# board.net
KiCad netlist of a schematic drawn in EAGLE
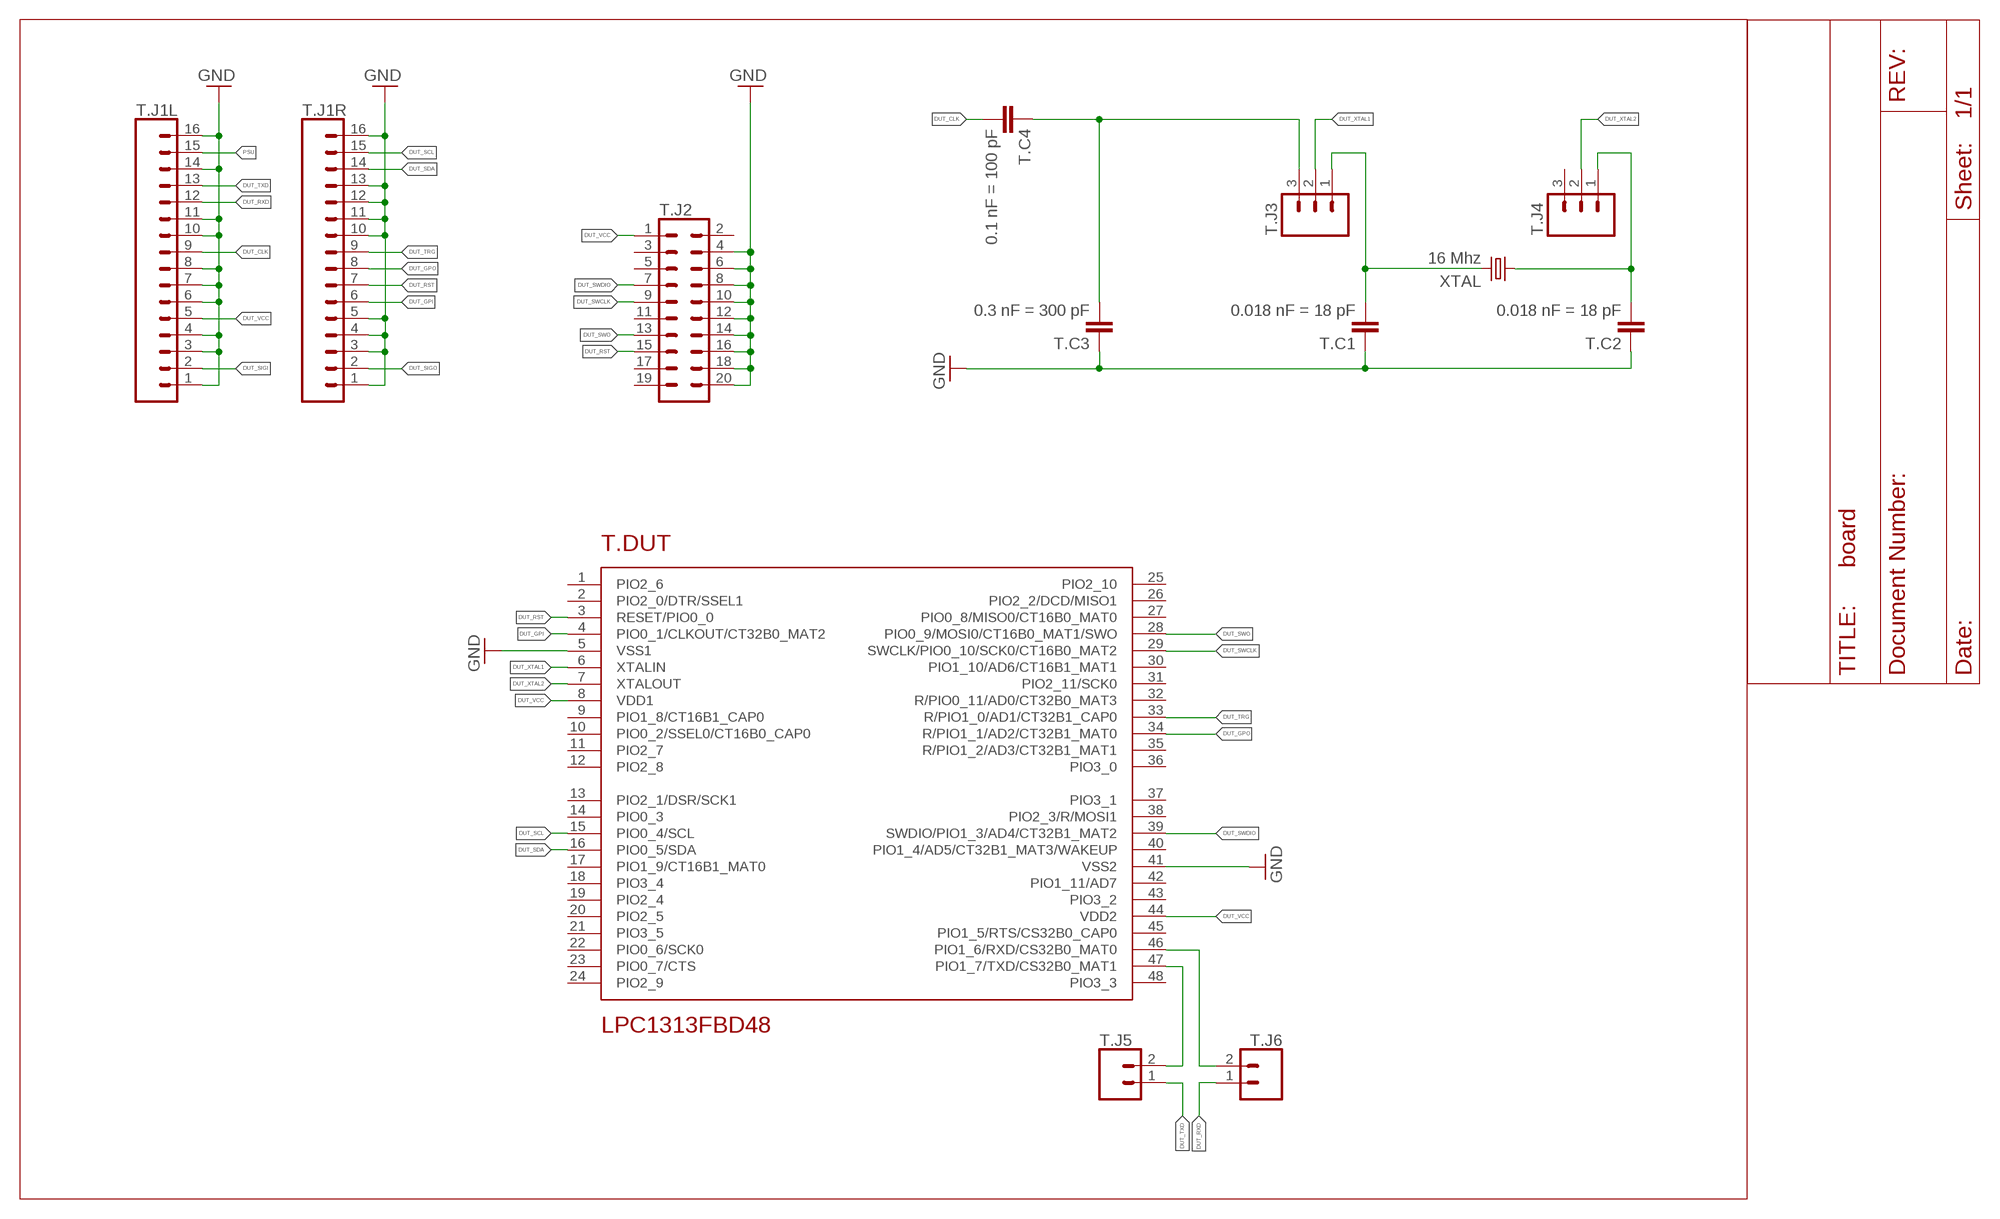
[diagram p0: schematic, sheet 1]

(export (version "E")
  (design (tool "Eeschema 10.0.6"))
  (components
    (comp (ref "T.C1")
      (value "0.018 nF = 18 pF")
      (footprint "eagle-import:0603-CAP")
      (libsource (lib "eagle-import") (part "CAP0603-CAP"))
    )
    (comp (ref "T.C2")
      (value "0.018 nF = 18 pF")
      (footprint "eagle-import:0603-CAP")
      (libsource (lib "eagle-import") (part "CAP0603-CAP"))
    )
    (comp (ref "T.C3")
      (value "0.3 nF = 300 pF")
      (footprint "eagle-import:0603-CAP")
      (libsource (lib "eagle-import") (part "CAP0603-CAP"))
    )
    (comp (ref "T.C4")
      (value "0.1 nF = 100 pF")
      (footprint "eagle-import:0603-CAP")
      (libsource (lib "eagle-import") (part "CAP0603-CAP"))
    )
    (comp (ref "T.DUT")
      (value "LPC1313FBD48")
      (footprint "eagle-import:LQFP48")
      (libsource (lib "eagle-import") (part "LPC1313FBD48"))
    )
    (comp (ref "T.J1L")
      (value "CONN_16")
      (footprint "eagle-import:1X16")
      (libsource (lib "eagle-import") (part "CONN_16"))
    )
    (comp (ref "T.J1R")
      (value "CONN_16")
      (footprint "eagle-import:1X16")
      (libsource (lib "eagle-import") (part "CONN_16"))
    )
    (comp (ref "T.J2")
      (value "CONN_10X2")
      (footprint "eagle-import:2X10")
      (libsource (lib "eagle-import") (part "CONN_10X2"))
    )
    (comp (ref "T.J3")
      (value "M03PTH")
      (footprint "eagle-import:1X03")
      (libsource (lib "eagle-import") (part "M03PTH"))
    )
    (comp (ref "T.J4")
      (value "M03PTH")
      (footprint "eagle-import:1X03")
      (libsource (lib "eagle-import") (part "M03PTH"))
    )
    (comp (ref "T.J5")
      (value "CONN_02")
      (footprint "eagle-import:1X02")
      (libsource (lib "eagle-import") (part "CONN_02"))
    )
    (comp (ref "T.J6")
      (value "CONN_02")
      (footprint "eagle-import:1X02")
      (libsource (lib "eagle-import") (part "CONN_02"))
    )
    (comp (ref "XTAL")
      (value "16 Mhz")
      (footprint "eagle-import:HC49US")
      (libsource (lib "eagle-import") (part "CRYSTALHC49US"))
    )
  )
  (nets
    (net (code "1") (name "DUT_CLK") (class "Default")
      (node (ref "T.C4") (pin "2") (pinfunction "2_2") (pintype "passive"))
      (node (ref "T.J1L") (pin "9") (pinfunction "9_9") (pintype "passive"))
    )
    (net (code "2") (name "DUT_GPI") (class "Default")
      (node (ref "T.DUT") (pin "4") (pinfunction "PIO0_1/CLKOUT/CT32B0_MAT2_4") (pintype "bidirectional"))
      (node (ref "T.J1R") (pin "6") (pinfunction "6_6") (pintype "passive"))
    )
    (net (code "3") (name "DUT_GPO") (class "Default")
      (node (ref "T.DUT") (pin "34") (pinfunction "R/PIO1_1/AD2/CT32B1_MAT0_34") (pintype "bidirectional"))
      (node (ref "T.J1R") (pin "8") (pinfunction "8_8") (pintype "passive"))
    )
    (net (code "4") (name "DUT_RST") (class "Default")
      (node (ref "T.DUT") (pin "3") (pinfunction "RESET/PIO0_0_3") (pintype "bidirectional"))
      (node (ref "T.J1R") (pin "7") (pinfunction "7_7") (pintype "passive"))
      (node (ref "T.J2") (pin "15") (pinfunction "15_15") (pintype "passive"))
    )
    (net (code "5") (name "DUT_RXD") (class "Default")
      (node (ref "T.J1L") (pin "12") (pinfunction "12_12") (pintype "passive"))
      (node (ref "T.J6") (pin "1") (pinfunction "1_1") (pintype "passive"))
    )
    (net (code "6") (name "DUT_SCL") (class "Default")
      (node (ref "T.DUT") (pin "15") (pinfunction "PIO0_4/SCL_15") (pintype "bidirectional"))
      (node (ref "T.J1R") (pin "15") (pinfunction "15_15") (pintype "passive"))
    )
    (net (code "7") (name "DUT_SDA") (class "Default")
      (node (ref "T.DUT") (pin "16") (pinfunction "PIO0_5/SDA_16") (pintype "bidirectional"))
      (node (ref "T.J1R") (pin "14") (pinfunction "14_14") (pintype "passive"))
    )
    (net (code "8") (name "DUT_SIGI") (class "Default")
      (node (ref "T.J1L") (pin "2") (pinfunction "2_2") (pintype "passive"))
    )
    (net (code "9") (name "DUT_SIGO") (class "Default")
      (node (ref "T.J1R") (pin "2") (pinfunction "2_2") (pintype "passive"))
    )
    (net (code "10") (name "DUT_SWCLK") (class "Default")
      (node (ref "T.DUT") (pin "29") (pinfunction "SWCLK/PIO0_10/SCK0/CT16B0_MAT2_29") (pintype "bidirectional"))
      (node (ref "T.J2") (pin "9") (pinfunction "9_9") (pintype "passive"))
    )
    (net (code "11") (name "DUT_SWDIO") (class "Default")
      (node (ref "T.DUT") (pin "39") (pinfunction "SWDIO/PIO1_3/AD4/CT32B1_MAT2_39") (pintype "bidirectional"))
      (node (ref "T.J2") (pin "7") (pinfunction "7_7") (pintype "passive"))
    )
    (net (code "12") (name "DUT_SWO") (class "Default")
      (node (ref "T.DUT") (pin "28") (pinfunction "PIO0_9/MOSI0/CT16B0_MAT1/SWO_28") (pintype "bidirectional"))
      (node (ref "T.J2") (pin "13") (pinfunction "13_13") (pintype "passive"))
    )
    (net (code "13") (name "DUT_TRG") (class "Default")
      (node (ref "T.DUT") (pin "33") (pinfunction "R/PIO1_0/AD1/CT32B1_CAP0_33") (pintype "bidirectional"))
      (node (ref "T.J1R") (pin "9") (pinfunction "9_9") (pintype "passive"))
    )
    (net (code "14") (name "DUT_TXD") (class "Default")
      (node (ref "T.J1L") (pin "13") (pinfunction "13_13") (pintype "passive"))
      (node (ref "T.J5") (pin "1") (pinfunction "1_1") (pintype "passive"))
    )
    (net (code "15") (name "DUT_VCC") (class "Default")
      (node (ref "T.DUT") (pin "44") (pinfunction "VDD2_44") (pintype "bidirectional"))
      (node (ref "T.DUT") (pin "8") (pinfunction "VDD1_8") (pintype "bidirectional"))
      (node (ref "T.J1L") (pin "5") (pinfunction "5_5") (pintype "passive"))
      (node (ref "T.J2") (pin "1") (pinfunction "1_1") (pintype "passive"))
    )
    (net (code "16") (name "DUT_XTAL1") (class "Default")
      (node (ref "T.DUT") (pin "6") (pinfunction "XTALIN_6") (pintype "bidirectional"))
      (node (ref "T.J3") (pin "2") (pinfunction "2_2") (pintype "passive"))
    )
    (net (code "17") (name "DUT_XTAL2") (class "Default")
      (node (ref "T.DUT") (pin "7") (pinfunction "XTALOUT_7") (pintype "bidirectional"))
      (node (ref "T.J4") (pin "2") (pinfunction "2_2") (pintype "passive"))
    )
    (net (code "18") (name "GND") (class "Default")
      (node (ref "T.C1") (pin "1") (pinfunction "1_1") (pintype "passive"))
      (node (ref "T.C2") (pin "1") (pinfunction "1_1") (pintype "passive"))
      (node (ref "T.C3") (pin "1") (pinfunction "1_1") (pintype "passive"))
      (node (ref "T.DUT") (pin "41") (pinfunction "VSS2_41") (pintype "bidirectional"))
      (node (ref "T.DUT") (pin "5") (pinfunction "VSS1_5") (pintype "bidirectional"))
      (node (ref "T.J1L") (pin "1") (pinfunction "1_1") (pintype "passive"))
      (node (ref "T.J1L") (pin "10") (pinfunction "10_10") (pintype "passive"))
      (node (ref "T.J1L") (pin "11") (pinfunction "11_11") (pintype "passive"))
      (node (ref "T.J1L") (pin "14") (pinfunction "14_14") (pintype "passive"))
      (node (ref "T.J1L") (pin "16") (pinfunction "16_16") (pintype "passive"))
      (node (ref "T.J1L") (pin "3") (pinfunction "3_3") (pintype "passive"))
      (node (ref "T.J1L") (pin "4") (pinfunction "4_4") (pintype "passive"))
      (node (ref "T.J1L") (pin "6") (pinfunction "6_6") (pintype "passive"))
      (node (ref "T.J1L") (pin "7") (pinfunction "7_7") (pintype "passive"))
      (node (ref "T.J1L") (pin "8") (pinfunction "8_8") (pintype "passive"))
      (node (ref "T.J1R") (pin "1") (pinfunction "1_1") (pintype "passive"))
      (node (ref "T.J1R") (pin "10") (pinfunction "10_10") (pintype "passive"))
      (node (ref "T.J1R") (pin "11") (pinfunction "11_11") (pintype "passive"))
      (node (ref "T.J1R") (pin "12") (pinfunction "12_12") (pintype "passive"))
      (node (ref "T.J1R") (pin "13") (pinfunction "13_13") (pintype "passive"))
      (node (ref "T.J1R") (pin "16") (pinfunction "16_16") (pintype "passive"))
      (node (ref "T.J1R") (pin "3") (pinfunction "3_3") (pintype "passive"))
      (node (ref "T.J1R") (pin "4") (pinfunction "4_4") (pintype "passive"))
      (node (ref "T.J1R") (pin "5") (pinfunction "5_5") (pintype "passive"))
      (node (ref "T.J2") (pin "10") (pinfunction "10_10") (pintype "passive"))
      (node (ref "T.J2") (pin "12") (pinfunction "12_12") (pintype "passive"))
      (node (ref "T.J2") (pin "14") (pinfunction "14_14") (pintype "passive"))
      (node (ref "T.J2") (pin "16") (pinfunction "16_16") (pintype "passive"))
      (node (ref "T.J2") (pin "18") (pinfunction "18_18") (pintype "passive"))
      (node (ref "T.J2") (pin "20") (pinfunction "20_20") (pintype "passive"))
      (node (ref "T.J2") (pin "4") (pinfunction "4_4") (pintype "passive"))
      (node (ref "T.J2") (pin "6") (pinfunction "6_6") (pintype "passive"))
      (node (ref "T.J2") (pin "8") (pinfunction "8_8") (pintype "passive"))
    )
    (net (code "19") (name "Net-(T.C1-Pad2)") (class "Default")
      (node (ref "T.C1") (pin "2") (pinfunction "2_2") (pintype "passive"))
      (node (ref "T.J3") (pin "1") (pinfunction "1_1") (pintype "passive"))
      (node (ref "XTAL") (pin "2") (pinfunction "2_2") (pintype "passive"))
    )
    (net (code "20") (name "Net-(T.C2-Pad2)") (class "Default")
      (node (ref "T.C2") (pin "2") (pinfunction "2_2") (pintype "passive"))
      (node (ref "T.J4") (pin "1") (pinfunction "1_1") (pintype "passive"))
      (node (ref "XTAL") (pin "1") (pinfunction "1_1") (pintype "passive"))
    )
    (net (code "21") (name "Net-(T.C3-Pad2)") (class "Default")
      (node (ref "T.C3") (pin "2") (pinfunction "2_2") (pintype "passive"))
      (node (ref "T.C4") (pin "1") (pinfunction "1_1") (pintype "passive"))
      (node (ref "T.J3") (pin "3") (pinfunction "3_3") (pintype "passive"))
    )
    (net (code "22") (name "Net-(T.DUT-PIO1_6{slash}RXD{slash}CS32B0_MAT0)") (class "Default")
      (node (ref "T.DUT") (pin "46") (pinfunction "PIO1_6/RXD/CS32B0_MAT0_46") (pintype "bidirectional"))
      (node (ref "T.J6") (pin "2") (pinfunction "2_2") (pintype "passive"))
    )
    (net (code "23") (name "Net-(T.DUT-PIO1_7{slash}TXD{slash}CS32B0_MAT1)") (class "Default")
      (node (ref "T.DUT") (pin "47") (pinfunction "PIO1_7/TXD/CS32B0_MAT1_47") (pintype "bidirectional"))
      (node (ref "T.J5") (pin "2") (pinfunction "2_2") (pintype "passive"))
    )
    (net (code "24") (name "PSU") (class "Default")
      (node (ref "T.J1L") (pin "15") (pinfunction "15_15") (pintype "passive"))
    )
    (net (code "25") (name "unconnected-(T.DUT-PIO0_2{slash}SSEL0{slash}CT16B0_CAP0-Pad10)") (class "Default")
      (node (ref "T.DUT") (pin "10") (pinfunction "PIO0_2/SSEL0/CT16B0_CAP0_10") (pintype "bidirectional"))
    )
    (net (code "26") (name "unconnected-(T.DUT-PIO0_3-Pad14)") (class "Default")
      (node (ref "T.DUT") (pin "14") (pinfunction "PIO0_3_14") (pintype "bidirectional"))
    )
    (net (code "27") (name "unconnected-(T.DUT-PIO0_6{slash}SCK0-Pad22)") (class "Default")
      (node (ref "T.DUT") (pin "22") (pinfunction "PIO0_6/SCK0_22") (pintype "bidirectional"))
    )
    (net (code "28") (name "unconnected-(T.DUT-PIO0_7{slash}CTS-Pad23)") (class "Default")
      (node (ref "T.DUT") (pin "23") (pinfunction "PIO0_7/CTS_23") (pintype "bidirectional"))
    )
    (net (code "29") (name "unconnected-(T.DUT-PIO0_8{slash}MISO0{slash}CT16B0_MAT0-Pad27)") (class "Default")
      (node (ref "T.DUT") (pin "27") (pinfunction "PIO0_8/MISO0/CT16B0_MAT0_27") (pintype "bidirectional"))
    )
    (net (code "30") (name "unconnected-(T.DUT-PIO1_4{slash}AD5{slash}CT32B1_MAT3{slash}WAKEUP-Pad40)") (class "Default")
      (node (ref "T.DUT") (pin "40") (pinfunction "PIO1_4/AD5/CT32B1_MAT3/WAKEUP_40") (pintype "bidirectional"))
    )
    (net (code "31") (name "unconnected-(T.DUT-PIO1_5{slash}RTS{slash}CS32B0_CAP0-Pad45)") (class "Default")
      (node (ref "T.DUT") (pin "45") (pinfunction "PIO1_5/RTS/CS32B0_CAP0_45") (pintype "bidirectional"))
    )
    (net (code "32") (name "unconnected-(T.DUT-PIO1_8{slash}CT16B1_CAP0-Pad9)") (class "Default")
      (node (ref "T.DUT") (pin "9") (pinfunction "PIO1_8/CT16B1_CAP0_9") (pintype "bidirectional"))
    )
    (net (code "33") (name "unconnected-(T.DUT-PIO1_9{slash}CT16B1_MAT0-Pad17)") (class "Default")
      (node (ref "T.DUT") (pin "17") (pinfunction "PIO1_9/CT16B1_MAT0_17") (pintype "bidirectional"))
    )
    (net (code "34") (name "unconnected-(T.DUT-PIO1_10{slash}AD6{slash}CT16B1_MAT1-Pad30)") (class "Default")
      (node (ref "T.DUT") (pin "30") (pinfunction "PIO1_10/AD6/CT16B1_MAT1_30") (pintype "bidirectional"))
    )
    (net (code "35") (name "unconnected-(T.DUT-PIO1_11{slash}AD7-Pad42)") (class "Default")
      (node (ref "T.DUT") (pin "42") (pinfunction "PIO1_11/AD7_42") (pintype "bidirectional"))
    )
    (net (code "36") (name "unconnected-(T.DUT-PIO2_0{slash}DTR{slash}SSEL1-Pad2)") (class "Default")
      (node (ref "T.DUT") (pin "2") (pinfunction "PIO2_0/DTR/SSEL1_2") (pintype "bidirectional"))
    )
    (net (code "37") (name "unconnected-(T.DUT-PIO2_1{slash}DSR{slash}SCK1-Pad13)") (class "Default")
      (node (ref "T.DUT") (pin "13") (pinfunction "PIO2_1/DSR/SCK1_13") (pintype "bidirectional"))
    )
    (net (code "38") (name "unconnected-(T.DUT-PIO2_2{slash}DCD{slash}MISO1-Pad26)") (class "Default")
      (node (ref "T.DUT") (pin "26") (pinfunction "PIO2_2/DCD/MISO1_26") (pintype "bidirectional"))
    )
    (net (code "39") (name "unconnected-(T.DUT-PIO2_3{slash}R{slash}MOSI1-Pad38)") (class "Default")
      (node (ref "T.DUT") (pin "38") (pinfunction "PIO2_3/R/MOSI1_38") (pintype "bidirectional"))
    )
    (net (code "40") (name "unconnected-(T.DUT-PIO2_4-Pad19)") (class "Default")
      (node (ref "T.DUT") (pin "19") (pinfunction "PIO2_4_19") (pintype "bidirectional"))
    )
    (net (code "41") (name "unconnected-(T.DUT-PIO2_5-Pad20)") (class "Default")
      (node (ref "T.DUT") (pin "20") (pinfunction "PIO2_5_20") (pintype "bidirectional"))
    )
    (net (code "42") (name "unconnected-(T.DUT-PIO2_6-Pad1)") (class "Default")
      (node (ref "T.DUT") (pin "1") (pinfunction "PIO2_6_1") (pintype "bidirectional"))
    )
    (net (code "43") (name "unconnected-(T.DUT-PIO2_7-Pad11)") (class "Default")
      (node (ref "T.DUT") (pin "11") (pinfunction "PIO2_7_11") (pintype "bidirectional"))
    )
    (net (code "44") (name "unconnected-(T.DUT-PIO2_8-Pad12)") (class "Default")
      (node (ref "T.DUT") (pin "12") (pinfunction "PIO2_8_12") (pintype "bidirectional"))
    )
    (net (code "45") (name "unconnected-(T.DUT-PIO2_9-Pad24)") (class "Default")
      (node (ref "T.DUT") (pin "24") (pinfunction "PIO2_9_24") (pintype "bidirectional"))
    )
    (net (code "46") (name "unconnected-(T.DUT-PIO2_10-Pad25)") (class "Default")
      (node (ref "T.DUT") (pin "25") (pinfunction "PIO2_10_25") (pintype "bidirectional"))
    )
    (net (code "47") (name "unconnected-(T.DUT-PIO2_11{slash}SCK0-Pad31)") (class "Default")
      (node (ref "T.DUT") (pin "31") (pinfunction "PIO2_11/SCK0_31") (pintype "bidirectional"))
    )
    (net (code "48") (name "unconnected-(T.DUT-PIO3_0-Pad36)") (class "Default")
      (node (ref "T.DUT") (pin "36") (pinfunction "PIO3_0_36") (pintype "bidirectional"))
    )
    (net (code "49") (name "unconnected-(T.DUT-PIO3_1-Pad37)") (class "Default")
      (node (ref "T.DUT") (pin "37") (pinfunction "PIO3_1_37") (pintype "bidirectional"))
    )
    (net (code "50") (name "unconnected-(T.DUT-PIO3_2-Pad43)") (class "Default")
      (node (ref "T.DUT") (pin "43") (pinfunction "PIO3_2_43") (pintype "bidirectional"))
    )
    (net (code "51") (name "unconnected-(T.DUT-PIO3_3-Pad48)") (class "Default")
      (node (ref "T.DUT") (pin "48") (pinfunction "PIO3_3_48") (pintype "bidirectional"))
    )
    (net (code "52") (name "unconnected-(T.DUT-PIO3_4-Pad18)") (class "Default")
      (node (ref "T.DUT") (pin "18") (pinfunction "PIO3_4_18") (pintype "bidirectional"))
    )
    (net (code "53") (name "unconnected-(T.DUT-PIO3_5-Pad21)") (class "Default")
      (node (ref "T.DUT") (pin "21") (pinfunction "PIO3_5_21") (pintype "bidirectional"))
    )
    (net (code "54") (name "unconnected-(T.DUT-R{slash}PIO0_11{slash}AD0{slash}CT32B0_MAT3-Pad32)") (class "Default")
      (node (ref "T.DUT") (pin "32") (pinfunction "R/PIO0_11/AD0/CT32B0_MAT3_32") (pintype "bidirectional"))
    )
    (net (code "55") (name "unconnected-(T.DUT-R{slash}PIO1_2{slash}AD3{slash}CT32B1_MAT1-Pad35)") (class "Default")
      (node (ref "T.DUT") (pin "35") (pinfunction "R/PIO1_2/AD3/CT32B1_MAT1_35") (pintype "bidirectional"))
    )
    (net (code "56") (name "unconnected-(T.J2-Pad2)") (class "Default")
      (node (ref "T.J2") (pin "2") (pinfunction "2_2") (pintype "passive"))
    )
    (net (code "57") (name "unconnected-(T.J2-Pad3)") (class "Default")
      (node (ref "T.J2") (pin "3") (pinfunction "3_3") (pintype "passive"))
    )
    (net (code "58") (name "unconnected-(T.J2-Pad5)") (class "Default")
      (node (ref "T.J2") (pin "5") (pinfunction "5_5") (pintype "passive"))
    )
    (net (code "59") (name "unconnected-(T.J2-Pad11)") (class "Default")
      (node (ref "T.J2") (pin "11") (pinfunction "11_11") (pintype "passive"))
    )
    (net (code "60") (name "unconnected-(T.J2-Pad17)") (class "Default")
      (node (ref "T.J2") (pin "17") (pinfunction "17_17") (pintype "passive"))
    )
    (net (code "61") (name "unconnected-(T.J2-Pad19)") (class "Default")
      (node (ref "T.J2") (pin "19") (pinfunction "19_19") (pintype "passive"))
    )
    (net (code "62") (name "unconnected-(T.J4-Pad3)") (class "Default")
      (node (ref "T.J4") (pin "3") (pinfunction "3_3") (pintype "passive"))
    )
  )
)
